# 09_Power_LDO.net
KiCad netlist of a schematic drawn in Altium Designer
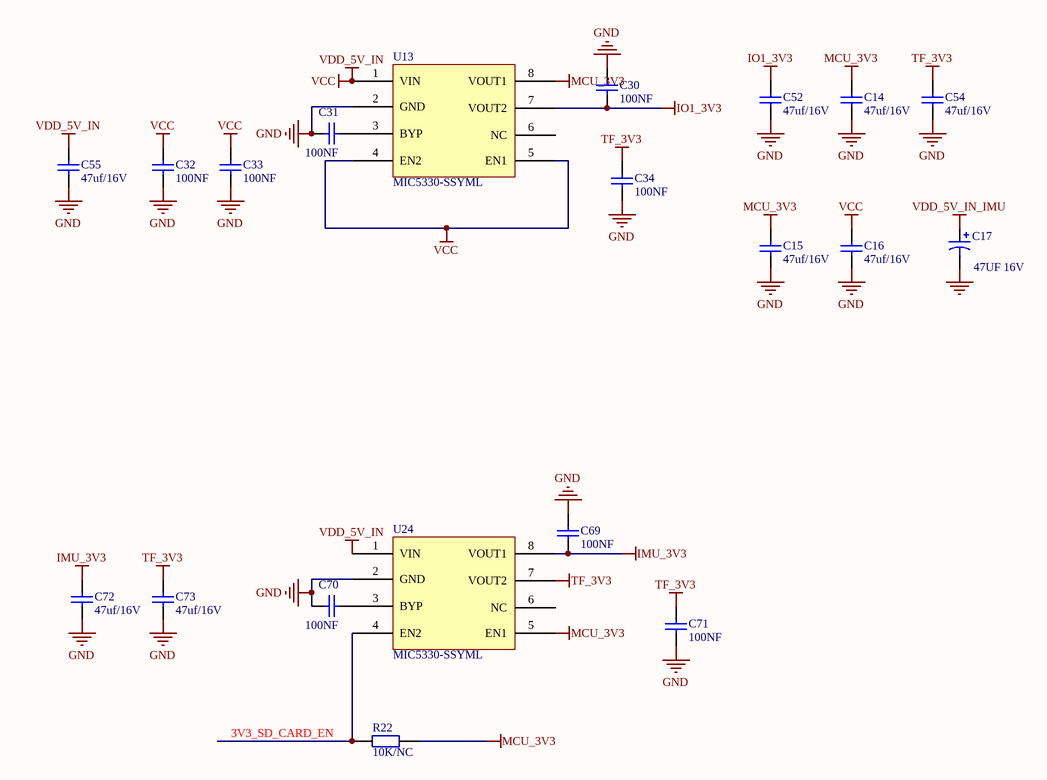
[diagram p0: 09_Power_LDO.SchDoc]

(export (version "E")
  (design (tool "Eeschema 10.0.6"))
  (components
    (comp (ref "C14")
      (value "47uf/16V")
      (description "Capacitor")
      (libsource (lib "Miscellaneous Devices") (part "Cap"))
    )
    (comp (ref "C15")
      (value "47uf/16V")
      (description "Capacitor")
      (libsource (lib "Miscellaneous Devices") (part "Cap"))
    )
    (comp (ref "C16")
      (value "47uf/16V")
      (description "Capacitor")
      (libsource (lib "Miscellaneous Devices") (part "Cap"))
    )
    (comp (ref "C17")
      (value "47UF 16V")
      (footprint "7343CAP")
      (description "T520V476M016ATE")
      (fields (field (name "PUBLISHER") "Altium Limited"))
      (libsource (lib "Miscellaneous Devices") (part "Cap Pol1"))
    )
    (comp (ref "C30")
      (value "100NF")
      (fields (field (name "PUBLISHER") "Altium Limited"))
      (libsource (lib "Miscellaneous Devices") (part "Cap"))
    )
    (comp (ref "C31")
      (value "100NF")
      (fields (field (name "PUBLISHER") "Altium Limited"))
      (libsource (lib "Miscellaneous Devices") (part "Cap"))
    )
    (comp (ref "C32")
      (value "100NF")
      (fields (field (name "PUBLISHER") "Altium Limited"))
      (libsource (lib "Miscellaneous Devices") (part "Cap"))
    )
    (comp (ref "C33")
      (value "100NF")
      (fields (field (name "PUBLISHER") "Altium Limited"))
      (libsource (lib "Miscellaneous Devices") (part "Cap"))
    )
    (comp (ref "C34") (value "100NF") (libsource (lib "Miscellaneous Devices") (part "Cap")))
    (comp (ref "C52")
      (value "47uf/16V")
      (description "Capacitor")
      (libsource (lib "Miscellaneous Devices") (part "Cap"))
    )
    (comp (ref "C54")
      (value "47uf/16V")
      (description "Capacitor")
      (libsource (lib "Miscellaneous Devices") (part "Cap"))
    )
    (comp (ref "C55")
      (value "47uf/16V")
      (description "Capacitor")
      (libsource (lib "Miscellaneous Devices") (part "Cap"))
    )
    (comp (ref "C69")
      (value "100NF")
      (fields (field (name "PUBLISHER") "Altium Limited"))
      (libsource (lib "Miscellaneous Devices") (part "Cap"))
    )
    (comp (ref "C70")
      (value "100NF")
      (fields (field (name "PUBLISHER") "Altium Limited"))
      (libsource (lib "Miscellaneous Devices") (part "Cap"))
    )
    (comp (ref "C71") (value "100NF") (libsource (lib "Miscellaneous Devices") (part "Cap")))
    (comp (ref "C72")
      (value "47uf/16V")
      (description "Capacitor")
      (libsource (lib "Miscellaneous Devices") (part "Cap"))
    )
    (comp (ref "C73")
      (value "47uf/16V")
      (description "Capacitor")
      (libsource (lib "Miscellaneous Devices") (part "Cap"))
    )
    (comp (ref "R22")
      (value "10K/NC")
      (footprint "0402R")
      (description "0402R10K 1%")
      (libsource (lib "CUAV") (part "0402R10K"))
    )
    (comp (ref "U13") (value "MIC5330-SSYML") (footprint "MIC5530") (libsource (lib "hack") (part "MIC5530")))
    (comp (ref "U24") (value "MIC5330-SSYML") (footprint "MIC5530") (libsource (lib "hack") (part "MIC5530")))
  )
  (nets
    (net (code "1") (name "/3V3_SD_CARD_EN") (class "Default")
      (node (ref "R22") (pin "2") (pintype "passive"))
      (node (ref "U24") (pin "4") (pinfunction "EN2_4") (pintype "passive"))
    )
    (net (code "2") (name "GND") (class "Default")
      (node (ref "C14") (pin "2") (pinfunction "2_2") (pintype "passive"))
      (node (ref "C15") (pin "2") (pinfunction "2_2") (pintype "passive"))
      (node (ref "C16") (pin "2") (pinfunction "2_2") (pintype "passive"))
      (node (ref "C17") (pin "C") (pinfunction "2_C") (pintype "passive"))
      (node (ref "C30") (pin "2") (pinfunction "2_2") (pintype "passive"))
      (node (ref "C31") (pin "2") (pinfunction "2_2") (pintype "passive"))
      (node (ref "C32") (pin "1") (pinfunction "1_1") (pintype "passive"))
      (node (ref "C33") (pin "1") (pinfunction "1_1") (pintype "passive"))
      (node (ref "C34") (pin "1") (pinfunction "1_1") (pintype "passive"))
      (node (ref "C52") (pin "2") (pinfunction "2_2") (pintype "passive"))
      (node (ref "C54") (pin "2") (pinfunction "2_2") (pintype "passive"))
      (node (ref "C55") (pin "2") (pinfunction "2_2") (pintype "passive"))
      (node (ref "C69") (pin "2") (pinfunction "2_2") (pintype "passive"))
      (node (ref "C70") (pin "2") (pinfunction "2_2") (pintype "passive"))
      (node (ref "C71") (pin "1") (pinfunction "1_1") (pintype "passive"))
      (node (ref "C72") (pin "2") (pinfunction "2_2") (pintype "passive"))
      (node (ref "C73") (pin "2") (pinfunction "2_2") (pintype "passive"))
      (node (ref "U13") (pin "2") (pinfunction "GND_2") (pintype "passive"))
      (node (ref "U24") (pin "2") (pinfunction "GND_2") (pintype "passive"))
    )
    (net (code "3") (name "IMU_3V3") (class "Default")
      (node (ref "C69") (pin "1") (pinfunction "1_1") (pintype "passive"))
      (node (ref "C72") (pin "1") (pinfunction "1_1") (pintype "passive"))
      (node (ref "U24") (pin "8") (pinfunction "VOUT1_8") (pintype "passive"))
    )
    (net (code "4") (name "IO1_3V3") (class "Default")
      (node (ref "C30") (pin "1") (pinfunction "1_1") (pintype "passive"))
      (node (ref "C52") (pin "1") (pinfunction "1_1") (pintype "passive"))
      (node (ref "U13") (pin "7") (pinfunction "VOUT2_7") (pintype "passive"))
    )
    (net (code "5") (name "MCU_3V3") (class "Default")
      (node (ref "C14") (pin "1") (pinfunction "1_1") (pintype "passive"))
      (node (ref "C15") (pin "1") (pinfunction "1_1") (pintype "passive"))
      (node (ref "R22") (pin "1") (pintype "passive"))
      (node (ref "U13") (pin "8") (pinfunction "VOUT1_8") (pintype "passive"))
      (node (ref "U24") (pin "5") (pinfunction "EN1_5") (pintype "passive"))
    )
    (net (code "6") (name "Net-(U13-BYP)") (class "Default")
      (node (ref "C31") (pin "1") (pinfunction "1_1") (pintype "passive"))
      (node (ref "U13") (pin "3") (pinfunction "BYP_3") (pintype "passive"))
    )
    (net (code "7") (name "Net-(U24-BYP)") (class "Default")
      (node (ref "C70") (pin "1") (pinfunction "1_1") (pintype "passive"))
      (node (ref "U24") (pin "3") (pinfunction "BYP_3") (pintype "passive"))
    )
    (net (code "8") (name "TF_3V3") (class "Default")
      (node (ref "C34") (pin "2") (pinfunction "2_2") (pintype "passive"))
      (node (ref "C54") (pin "1") (pinfunction "1_1") (pintype "passive"))
      (node (ref "C71") (pin "2") (pinfunction "2_2") (pintype "passive"))
      (node (ref "C73") (pin "1") (pinfunction "1_1") (pintype "passive"))
      (node (ref "U24") (pin "7") (pinfunction "VOUT2_7") (pintype "passive"))
    )
    (net (code "9") (name "VCC") (class "Default")
      (node (ref "C16") (pin "1") (pinfunction "1_1") (pintype "passive"))
      (node (ref "C32") (pin "2") (pinfunction "2_2") (pintype "passive"))
      (node (ref "C33") (pin "2") (pinfunction "2_2") (pintype "passive"))
      (node (ref "C55") (pin "1") (pinfunction "1_1") (pintype "passive"))
      (node (ref "U13") (pin "1") (pinfunction "VIN_1") (pintype "passive"))
      (node (ref "U13") (pin "4") (pinfunction "EN2_4") (pintype "passive"))
      (node (ref "U13") (pin "5") (pinfunction "EN1_5") (pintype "passive"))
      (node (ref "U24") (pin "1") (pinfunction "VIN_1") (pintype "passive"))
    )
    (net (code "10") (name "VDD_5V_IN_IMU") (class "Default")
      (node (ref "C17") (pin "A") (pinfunction "1_A") (pintype "passive"))
    )
    (net (code "11") (name "unconnected-(U13-NC-Pad6)") (class "Default")
      (node (ref "U13") (pin "6") (pinfunction "NC_6") (pintype "passive"))
    )
    (net (code "12") (name "unconnected-(U24-NC-Pad6)") (class "Default")
      (node (ref "U24") (pin "6") (pinfunction "NC_6") (pintype "passive"))
    )
  )
)
